# Proto.net
KiCad netlist of a schematic drawn in Altium Designer
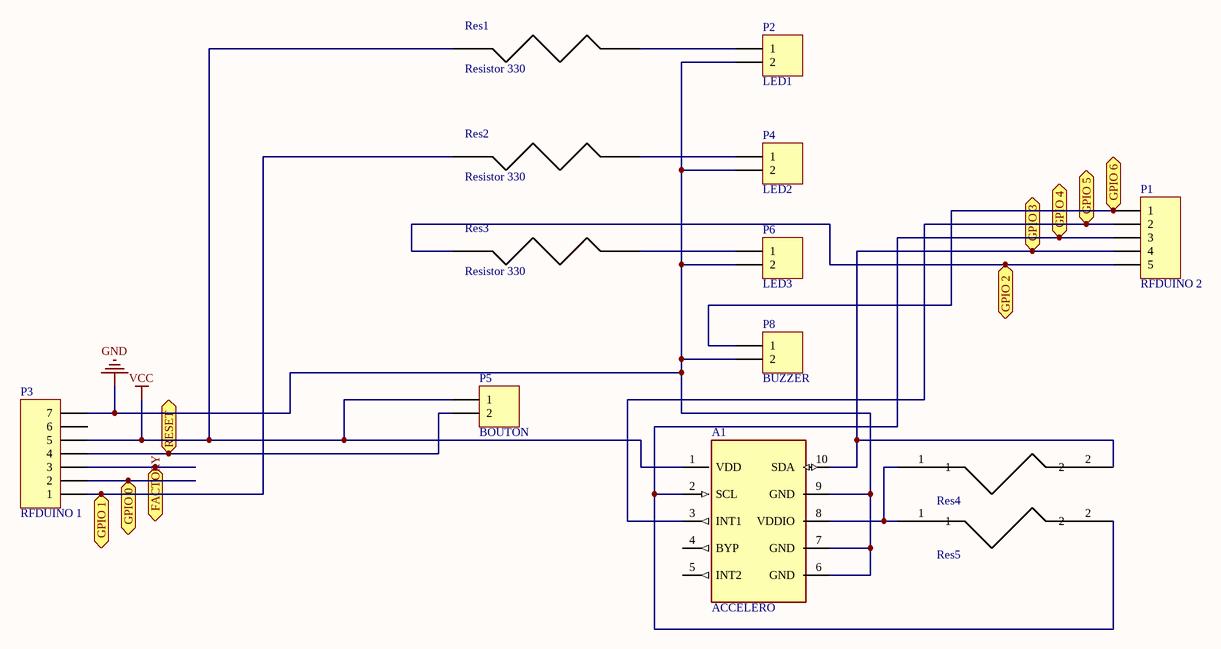
[diagram p0: Proto.SchDoc]

(export (version "E")
  (design (tool "Eeschema 10.0.6"))
  (components
    (comp (ref "A1")
      (value "ACCELERO")
      (footprint "SON40P200X100-10M")
      (description "Accéléromètres 3-axis 2g/4g/8g 10 bit")
      (fields (field (name "MANUFACTURER") "NXP / Freescale") (field (name "PUBLISHER") "François Lefevre"))
      (libsource (lib "Integrated_Library") (part "MMA8653FCR1"))
    )
    (comp (ref "P1")
      (value "RFDUINO 2")
      (footprint "HDR1X5")
      (description "Header, 5-Pin")
      (fields (field (name "PUBLISHER") "Altium Limited"))
      (libsource (lib "Miscellaneous Connectors") (part "Header 5"))
    )
    (comp (ref "P2")
      (value "LED1")
      (footprint "HDR1X2")
      (description "Header, 2-Pin")
      (fields (field (name "PUBLISHER") "Altium Limited"))
      (libsource (lib "Miscellaneous Connectors") (part "Header 2"))
    )
    (comp (ref "P3")
      (value "RFDUINO 1")
      (footprint "HDR1X7")
      (description "Header, 7-Pin")
      (fields (field (name "PUBLISHER") "Altium Limited"))
      (libsource (lib "Miscellaneous Connectors") (part "Header 7"))
    )
    (comp (ref "P4")
      (value "LED2")
      (footprint "HDR1X2")
      (description "Header, 2-Pin")
      (fields (field (name "PUBLISHER") "Altium Limited"))
      (libsource (lib "Miscellaneous Connectors") (part "Header 2"))
    )
    (comp (ref "P5")
      (value "BOUTON")
      (footprint "HDR1X2")
      (description "Header, 2-Pin")
      (fields (field (name "PUBLISHER") "Altium Limited"))
      (libsource (lib "Miscellaneous Connectors") (part "Header 2"))
    )
    (comp (ref "P6")
      (value "LED3")
      (footprint "HDR1X2")
      (description "Header, 2-Pin")
      (fields (field (name "PUBLISHER") "Altium Limited"))
      (libsource (lib "Miscellaneous Connectors") (part "Header 2"))
    )
    (comp (ref "P8")
      (value "BUZZER")
      (footprint "HDR1X2")
      (description "Header, 2-Pin")
      (fields (field (name "PUBLISHER") "Altium Limited"))
      (libsource (lib "Miscellaneous Connectors") (part "Header 2"))
    )
    (comp (ref "Res1")
      (value "Resistor 330")
      (footprint "RESC3116X06M")
      (description "Résistance CMS 330 Ohms  250 mW  size 1206 taille 3.2x1.6 mm série CRCW")
      (fields
        (field (name "MANUFACTURER") "Mouser")
        (field (name "MANUFACTURER PART NUMBER") "CRCW1206330RFKEA")
        (field (name "PUBLISHER") "François Lefevre")
      )
      (libsource (lib "Integrated_Library") (part "CRCW1206330RFKEA"))
    )
    (comp (ref "Res2")
      (value "Resistor 330")
      (footprint "RESC3116X06M")
      (description "Résistance CMS 330 Ohms  250 mW  size 1206 taille 3.2x1.6 mm série CRCW")
      (fields
        (field (name "MANUFACTURER") "Mouser")
        (field (name "MANUFACTURER PART NUMBER") "CRCW1206330RFKEA")
        (field (name "PUBLISHER") "François Lefevre")
      )
      (libsource (lib "Integrated_Library") (part "CRCW1206330RFKEA"))
    )
    (comp (ref "Res3")
      (value "Resistor 330")
      (footprint "RESC3116X06M")
      (description "Résistance CMS 330 Ohms  250 mW  size 1206 taille 3.2x1.6 mm série CRCW")
      (fields
        (field (name "MANUFACTURER") "Mouser")
        (field (name "MANUFACTURER PART NUMBER") "CRCW1206330RFKEA")
        (field (name "PUBLISHER") "François Lefevre")
      )
      (libsource (lib "Integrated_Library") (part "CRCW1206330RFKEA"))
    )
    (comp (ref "Res4")
      (value "res 1Kohms 0603 CMS")
      (footprint "RESC1608X06M")
      (libsource (lib "Integrated_Library") (part "Res1000"))
    )
    (comp (ref "Res5")
      (value "res 1Kohms 0603 CMS")
      (footprint "RESC1608X06M")
      (libsource (lib "Integrated_Library") (part "Res1000"))
    )
  )
  (nets
    (net (code "1") (name "/FACTORY") (class "Default")
      (node (ref "P3") (pin "3") (pinfunction "3_3") (pintype "passive"))
    )
    (net (code "2") (name "/GPIO 0") (class "Default")
      (node (ref "P3") (pin "2") (pinfunction "2_2") (pintype "passive"))
    )
    (net (code "3") (name "/GPIO 1") (class "Default")
      (node (ref "P3") (pin "1") (pinfunction "1_1") (pintype "passive"))
      (node (ref "Res2") (pin "1") (pinfunction "I/O_1") (pintype "passive"))
    )
    (net (code "4") (name "/GPIO 2") (class "Default")
      (node (ref "P1") (pin "5") (pinfunction "5_5") (pintype "passive"))
      (node (ref "Res3") (pin "1") (pinfunction "I/O_1") (pintype "passive"))
    )
    (net (code "5") (name "/GPIO 3") (class "Default")
      (node (ref "A1") (pin "10") (pinfunction "SDA_10") (pintype "bidirectional"))
      (node (ref "P1") (pin "4") (pinfunction "4_4") (pintype "passive"))
      (node (ref "Res4") (pin "2") (pinfunction "2_2") (pintype "passive"))
    )
    (net (code "6") (name "/GPIO 4") (class "Default")
      (node (ref "A1") (pin "2") (pinfunction "SCL_2") (pintype "input"))
      (node (ref "P1") (pin "3") (pinfunction "3_3") (pintype "passive"))
      (node (ref "Res5") (pin "2") (pinfunction "2_2") (pintype "passive"))
    )
    (net (code "7") (name "/GPIO 5") (class "Default")
      (node (ref "A1") (pin "3") (pinfunction "INT1_3") (pintype "output"))
      (node (ref "P1") (pin "2") (pinfunction "2_2") (pintype "passive"))
    )
    (net (code "8") (name "/GPIO 6") (class "Default")
      (node (ref "P1") (pin "1") (pinfunction "1_1") (pintype "passive"))
      (node (ref "P8") (pin "1") (pinfunction "1_1") (pintype "passive"))
    )
    (net (code "9") (name "/RESET") (class "Default")
      (node (ref "P3") (pin "4") (pinfunction "4_4") (pintype "passive"))
      (node (ref "P5") (pin "2") (pinfunction "2_2") (pintype "passive"))
    )
    (net (code "10") (name "GND") (class "Default")
      (node (ref "A1") (pin "6") (pinfunction "GND_6") (pintype "power_in"))
      (node (ref "A1") (pin "7") (pinfunction "GND_7") (pintype "power_in"))
      (node (ref "A1") (pin "9") (pinfunction "GND_9") (pintype "power_in"))
      (node (ref "P2") (pin "2") (pinfunction "2_2") (pintype "passive"))
      (node (ref "P3") (pin "7") (pinfunction "7_7") (pintype "passive"))
      (node (ref "P4") (pin "2") (pinfunction "2_2") (pintype "passive"))
      (node (ref "P6") (pin "2") (pinfunction "2_2") (pintype "passive"))
      (node (ref "P8") (pin "2") (pinfunction "2_2") (pintype "passive"))
    )
    (net (code "11") (name "Net-(A1-VDDIO)") (class "Default")
      (node (ref "A1") (pin "8") (pinfunction "VDDIO_8") (pintype "power_in"))
      (node (ref "Res4") (pin "1") (pinfunction "1_1") (pintype "passive"))
      (node (ref "Res5") (pin "1") (pinfunction "1_1") (pintype "passive"))
    )
    (net (code "12") (name "Net-(P2-Pad1)") (class "Default")
      (node (ref "P2") (pin "1") (pinfunction "1_1") (pintype "passive"))
      (node (ref "Res1") (pin "2") (pinfunction "I/O_2") (pintype "passive"))
    )
    (net (code "13") (name "Net-(P4-Pad1)") (class "Default")
      (node (ref "P4") (pin "1") (pinfunction "1_1") (pintype "passive"))
      (node (ref "Res2") (pin "2") (pinfunction "I/O_2") (pintype "passive"))
    )
    (net (code "14") (name "Net-(P6-Pad1)") (class "Default")
      (node (ref "P6") (pin "1") (pinfunction "1_1") (pintype "passive"))
      (node (ref "Res3") (pin "2") (pinfunction "I/O_2") (pintype "passive"))
    )
    (net (code "15") (name "VCC") (class "Default")
      (node (ref "A1") (pin "1") (pinfunction "VDD_1") (pintype "power_in"))
      (node (ref "P3") (pin "5") (pinfunction "5_5") (pintype "passive"))
      (node (ref "P5") (pin "1") (pinfunction "1_1") (pintype "passive"))
      (node (ref "Res1") (pin "1") (pinfunction "I/O_1") (pintype "passive"))
    )
    (net (code "16") (name "unconnected-(A1-BYP-Pad4)") (class "Default")
      (node (ref "A1") (pin "4") (pinfunction "BYP_4") (pintype "output"))
    )
    (net (code "17") (name "unconnected-(A1-INT2-Pad5)") (class "Default")
      (node (ref "A1") (pin "5") (pinfunction "INT2_5") (pintype "output"))
    )
    (net (code "18") (name "unconnected-(P3-Pad6)") (class "Default")
      (node (ref "P3") (pin "6") (pinfunction "6_6") (pintype "passive"))
    )
  )
)
